# 1-Schematic_video_multiple.net
KiCad netlist of a schematic drawn in EasyEDA
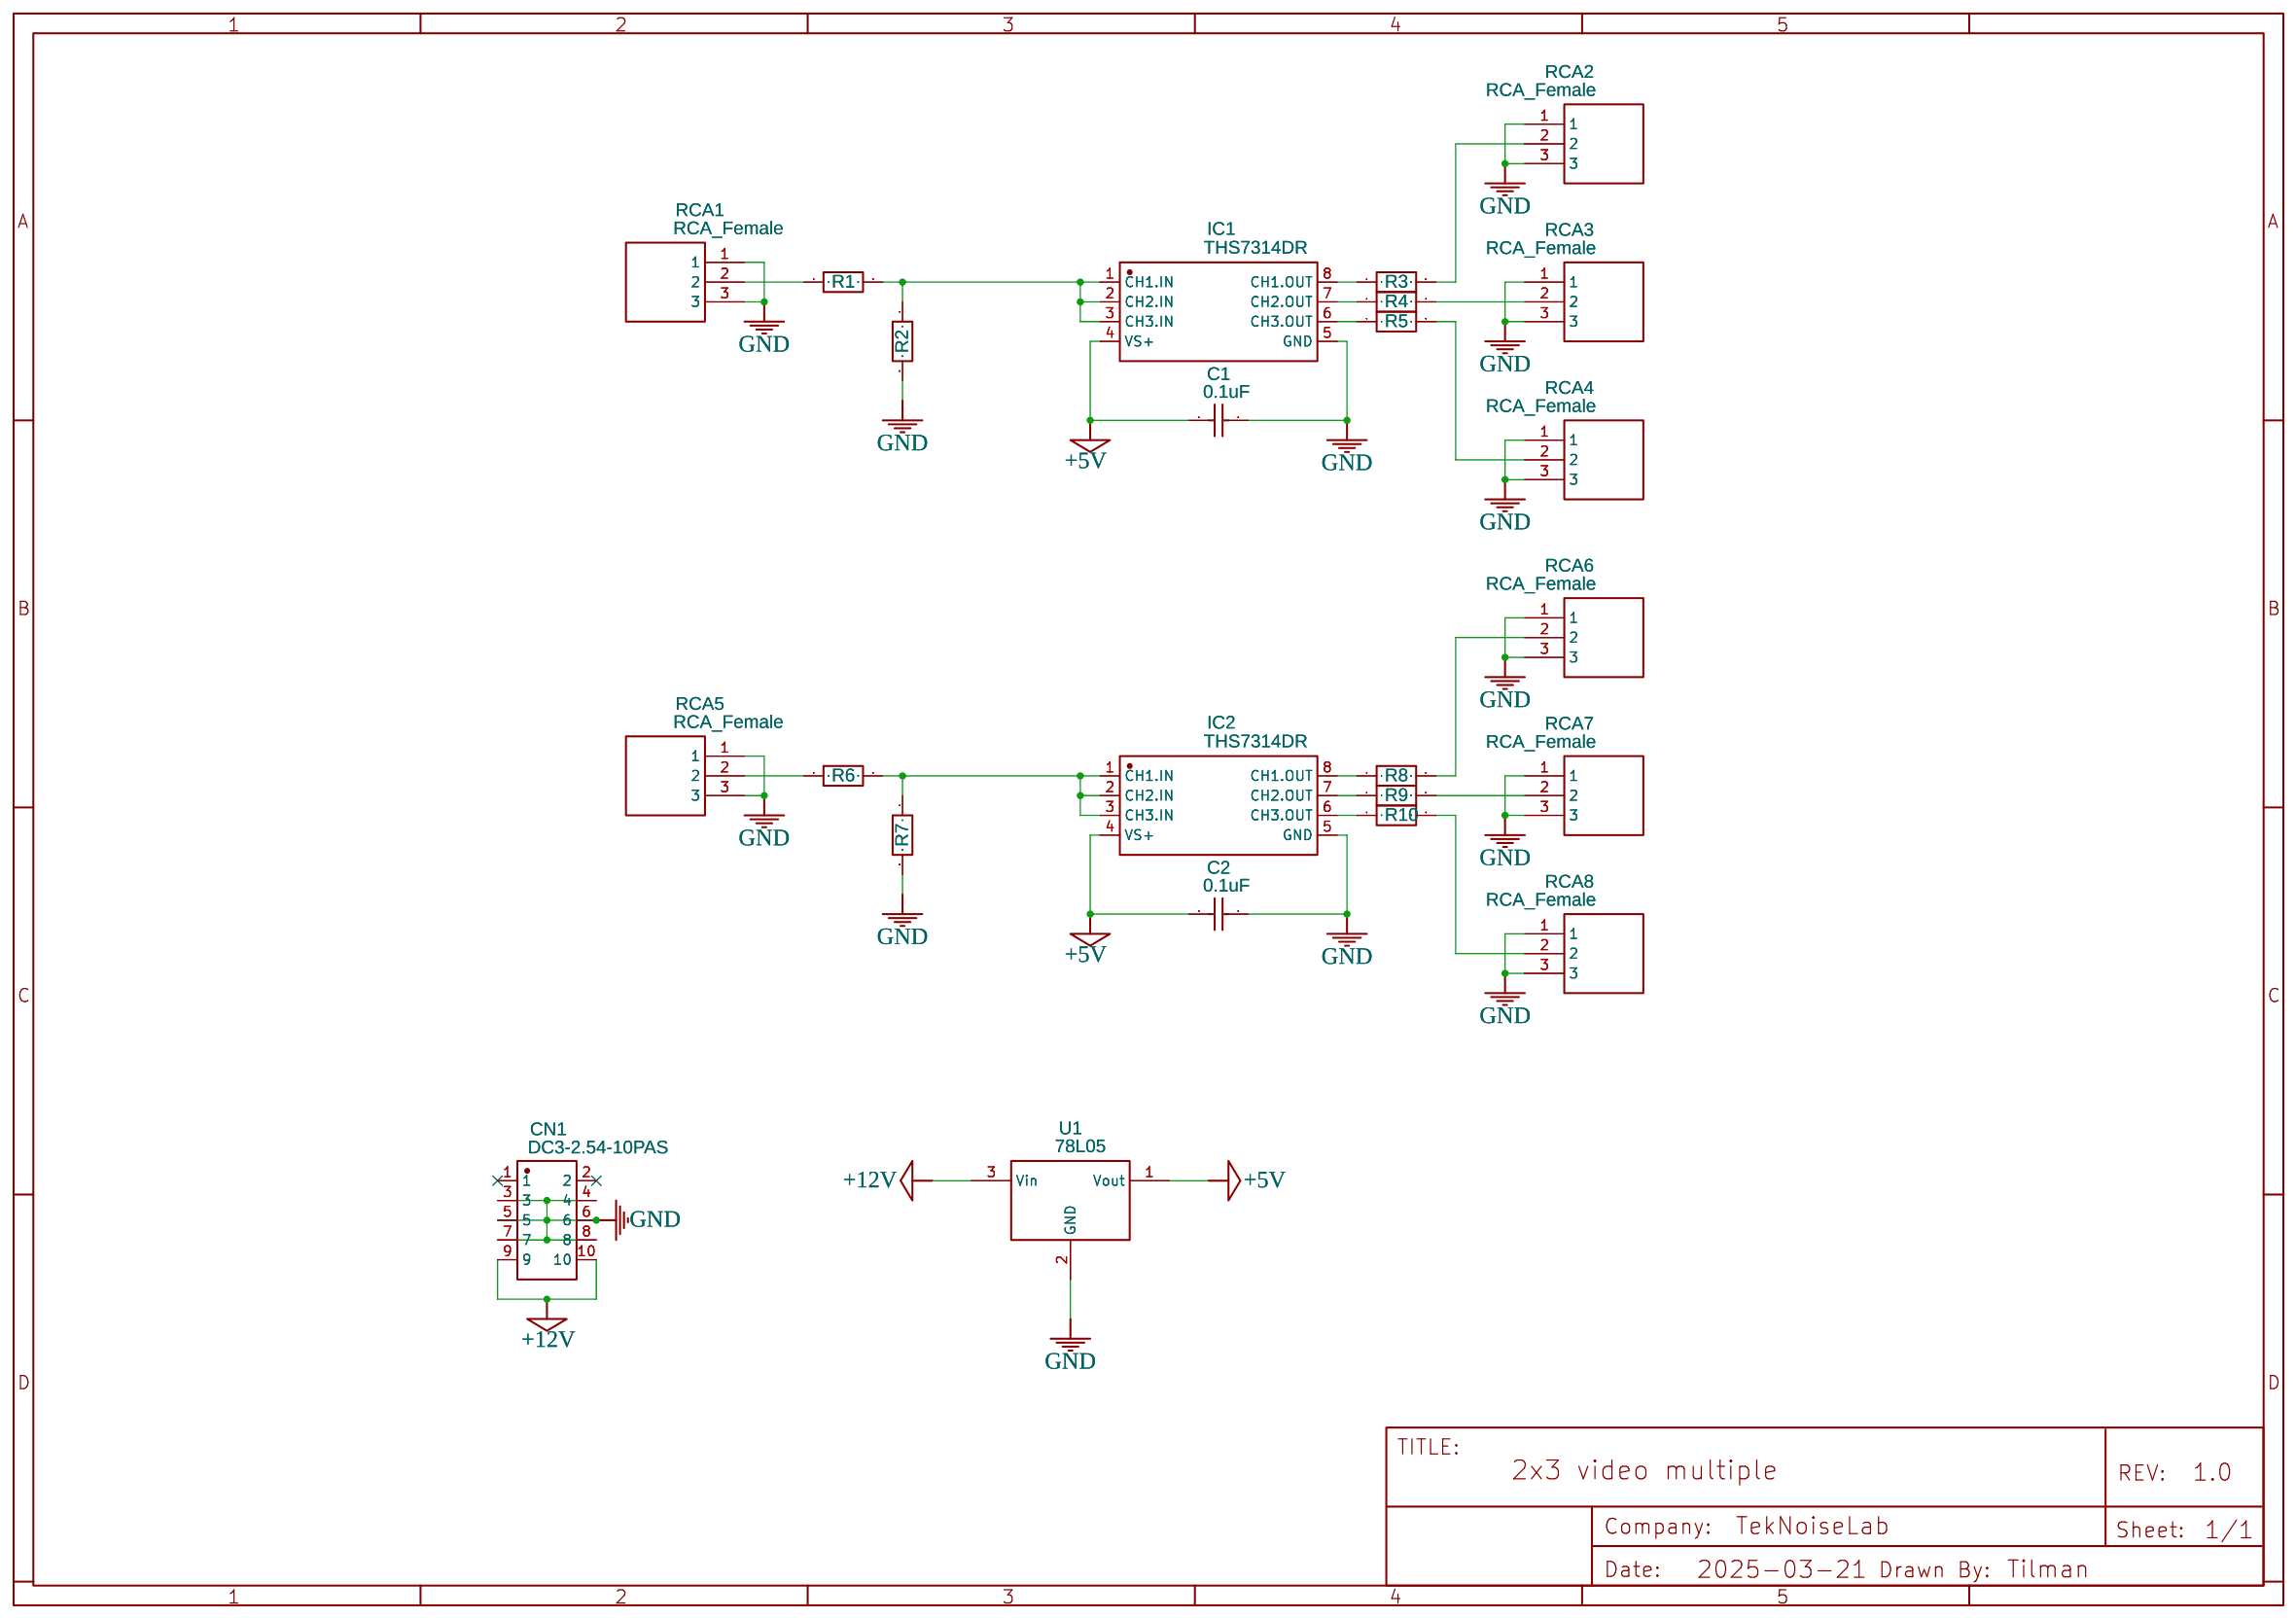
[diagram p0: schematic sheet]

(export (version "E")
  (design (tool "Eeschema 10.0.6"))
  (components
    (comp (ref "C1")
      (value "0.1uF")
      (fields
        (field (name "Manufacturer Part") "0.22uF 5% 100VCalibration capacitor")
        (field (name "Manufacturer") "ReliaPro")
      )
      (libsource (lib "") (part "0.22uF 5% 100VCalibration capacitor"))
    )
    (comp (ref "C2")
      (value "0.1uF")
      (fields
        (field (name "Manufacturer Part") "0.22uF 5% 100VCalibration capacitor")
        (field (name "Manufacturer") "ReliaPro")
      )
      (libsource (lib "") (part "0.22uF 5% 100VCalibration capacitor"))
    )
    (comp (ref "CN1")
      (value "DC3-2.54-10PAS")
      (fields (field (name "Manufacturer") "ZHOURI(洲日)"))
      (libsource (lib "") (part "DC3-2.54-10PAS"))
    )
    (comp (ref "IC1")
      (value "THS7314DR")
      (fields (field (name "Manufacturer") "TI(德州仪器)"))
      (libsource (lib "") (part "THS7314DR"))
    )
    (comp (ref "IC2")
      (value "THS7314DR")
      (fields (field (name "Manufacturer") "TI(德州仪器)"))
      (libsource (lib "") (part "THS7314DR"))
    )
    (comp (ref "R1") (value "75") (libsource (lib "") (part "Res_AXIAL-0.4(1/4W)_US")))
    (comp (ref "R2") (value "75") (libsource (lib "") (part "Res_AXIAL-0.4(1/4W)_US_1")))
    (comp (ref "R3") (value "75") (libsource (lib "") (part "Res_AXIAL-0.4(1/4W)_US")))
    (comp (ref "R4") (value "75") (libsource (lib "") (part "Res_AXIAL-0.4(1/4W)_US")))
    (comp (ref "R5") (value "75") (libsource (lib "") (part "Res_AXIAL-0.4(1/4W)_US")))
    (comp (ref "R6") (value "75") (libsource (lib "") (part "Res_AXIAL-0.4(1/4W)_US")))
    (comp (ref "R7") (value "75") (libsource (lib "") (part "Res_AXIAL-0.4(1/4W)_US_1")))
    (comp (ref "R8") (value "75") (libsource (lib "") (part "Res_AXIAL-0.4(1/4W)_US")))
    (comp (ref "R9") (value "75") (libsource (lib "") (part "Res_AXIAL-0.4(1/4W)_US")))
    (comp (ref "R10") (value "75") (libsource (lib "") (part "Res_AXIAL-0.4(1/4W)_US")))
    (comp (ref "RCA1") (value "RCA_Female") (libsource (lib "") (part "RCA_Female")))
    (comp (ref "RCA2") (value "RCA_Female") (libsource (lib "") (part "RCA_Female_1")))
    (comp (ref "RCA3") (value "RCA_Female") (libsource (lib "") (part "RCA_Female_1")))
    (comp (ref "RCA4") (value "RCA_Female") (libsource (lib "") (part "RCA_Female_1")))
    (comp (ref "RCA5") (value "RCA_Female") (libsource (lib "") (part "RCA_Female")))
    (comp (ref "RCA6") (value "RCA_Female") (libsource (lib "") (part "RCA_Female_1")))
    (comp (ref "RCA7") (value "RCA_Female") (libsource (lib "") (part "RCA_Female_1")))
    (comp (ref "RCA8") (value "RCA_Female") (libsource (lib "") (part "RCA_Female_1")))
    (comp (ref "U1")
      (value "78L05")
      (fields
        (field (name "Manufacturer Part") "SN78L05AT")
        (field (name "Manufacturer") "KODENSHI AUK(光电子)")
      )
      (libsource (lib "") (part "SN78L05AT"))
    )
  )
  (nets
    (net (code "1") (name "+5V") (class "Default")
      (node (ref "C1") (pin "1") (pinfunction "1_1") (pintype "input"))
      (node (ref "C2") (pin "1") (pinfunction "1_1") (pintype "input"))
      (node (ref "IC1") (pin "4") (pinfunction "VS+_4") (pintype "unspecified"))
      (node (ref "IC2") (pin "4") (pinfunction "VS+_4") (pintype "unspecified"))
      (node (ref "U1") (pin "1") (pinfunction "Vout_1") (pintype "unspecified"))
    )
    (net (code "2") (name "+12V") (class "Default")
      (node (ref "CN1") (pin "10") (pinfunction "10_10") (pintype "unspecified"))
      (node (ref "CN1") (pin "9") (pinfunction "9_9") (pintype "unspecified"))
      (node (ref "U1") (pin "3") (pinfunction "Vin_3") (pintype "unspecified"))
    )
    (net (code "3") (name "GND") (class "Default")
      (node (ref "C1") (pin "2") (pinfunction "2_2") (pintype "input"))
      (node (ref "C2") (pin "2") (pinfunction "2_2") (pintype "input"))
      (node (ref "CN1") (pin "3") (pinfunction "3_3") (pintype "unspecified"))
      (node (ref "CN1") (pin "4") (pinfunction "4_4") (pintype "unspecified"))
      (node (ref "CN1") (pin "5") (pinfunction "5_5") (pintype "unspecified"))
      (node (ref "CN1") (pin "6") (pinfunction "6_6") (pintype "unspecified"))
      (node (ref "CN1") (pin "7") (pinfunction "7_7") (pintype "unspecified"))
      (node (ref "CN1") (pin "8") (pinfunction "8_8") (pintype "unspecified"))
      (node (ref "IC1") (pin "5") (pinfunction "GND_5") (pintype "unspecified"))
      (node (ref "IC2") (pin "5") (pinfunction "GND_5") (pintype "unspecified"))
      (node (ref "R2") (pin "2") (pinfunction "2_2") (pintype "unspecified"))
      (node (ref "R7") (pin "2") (pinfunction "2_2") (pintype "unspecified"))
      (node (ref "RCA1") (pin "1") (pinfunction "1_1") (pintype "unspecified"))
      (node (ref "RCA1") (pin "3") (pinfunction "3_3") (pintype "unspecified"))
      (node (ref "RCA2") (pin "1") (pinfunction "1_1") (pintype "unspecified"))
      (node (ref "RCA2") (pin "3") (pinfunction "3_3") (pintype "unspecified"))
      (node (ref "RCA3") (pin "1") (pinfunction "1_1") (pintype "unspecified"))
      (node (ref "RCA3") (pin "3") (pinfunction "3_3") (pintype "unspecified"))
      (node (ref "RCA4") (pin "1") (pinfunction "1_1") (pintype "unspecified"))
      (node (ref "RCA4") (pin "3") (pinfunction "3_3") (pintype "unspecified"))
      (node (ref "RCA5") (pin "1") (pinfunction "1_1") (pintype "unspecified"))
      (node (ref "RCA5") (pin "3") (pinfunction "3_3") (pintype "unspecified"))
      (node (ref "RCA6") (pin "1") (pinfunction "1_1") (pintype "unspecified"))
      (node (ref "RCA6") (pin "3") (pinfunction "3_3") (pintype "unspecified"))
      (node (ref "RCA7") (pin "1") (pinfunction "1_1") (pintype "unspecified"))
      (node (ref "RCA7") (pin "3") (pinfunction "3_3") (pintype "unspecified"))
      (node (ref "RCA8") (pin "1") (pinfunction "1_1") (pintype "unspecified"))
      (node (ref "RCA8") (pin "3") (pinfunction "3_3") (pintype "unspecified"))
      (node (ref "U1") (pin "2") (pinfunction "GND_2") (pintype "unspecified"))
    )
    (net (code "4") (name "Net-(IC1-CH1.IN)") (class "Default")
      (node (ref "IC1") (pin "1") (pinfunction "CH1.IN_1") (pintype "unspecified"))
      (node (ref "IC1") (pin "2") (pinfunction "CH2.IN_2") (pintype "unspecified"))
      (node (ref "IC1") (pin "3") (pinfunction "CH3.IN_3") (pintype "unspecified"))
      (node (ref "R1") (pin "2") (pinfunction "2_2") (pintype "unspecified"))
      (node (ref "R2") (pin "1") (pinfunction "1_1") (pintype "unspecified"))
    )
    (net (code "5") (name "Net-(IC1-CH1.OUT)") (class "Default")
      (node (ref "IC1") (pin "8") (pinfunction "CH1.OUT_8") (pintype "unspecified"))
      (node (ref "R3") (pin "1") (pinfunction "1_1") (pintype "unspecified"))
    )
    (net (code "6") (name "Net-(IC1-CH2.OUT)") (class "Default")
      (node (ref "IC1") (pin "7") (pinfunction "CH2.OUT_7") (pintype "unspecified"))
      (node (ref "R4") (pin "1") (pinfunction "1_1") (pintype "unspecified"))
    )
    (net (code "7") (name "Net-(IC1-CH3.OUT)") (class "Default")
      (node (ref "IC1") (pin "6") (pinfunction "CH3.OUT_6") (pintype "unspecified"))
      (node (ref "R5") (pin "1") (pinfunction "1_1") (pintype "unspecified"))
    )
    (net (code "8") (name "Net-(IC2-CH1.IN)") (class "Default")
      (node (ref "IC2") (pin "1") (pinfunction "CH1.IN_1") (pintype "unspecified"))
      (node (ref "IC2") (pin "2") (pinfunction "CH2.IN_2") (pintype "unspecified"))
      (node (ref "IC2") (pin "3") (pinfunction "CH3.IN_3") (pintype "unspecified"))
      (node (ref "R6") (pin "2") (pinfunction "2_2") (pintype "unspecified"))
      (node (ref "R7") (pin "1") (pinfunction "1_1") (pintype "unspecified"))
    )
    (net (code "9") (name "Net-(IC2-CH1.OUT)") (class "Default")
      (node (ref "IC2") (pin "8") (pinfunction "CH1.OUT_8") (pintype "unspecified"))
      (node (ref "R8") (pin "1") (pinfunction "1_1") (pintype "unspecified"))
    )
    (net (code "10") (name "Net-(IC2-CH2.OUT)") (class "Default")
      (node (ref "IC2") (pin "7") (pinfunction "CH2.OUT_7") (pintype "unspecified"))
      (node (ref "R9") (pin "1") (pinfunction "1_1") (pintype "unspecified"))
    )
    (net (code "11") (name "Net-(IC2-CH3.OUT)") (class "Default")
      (node (ref "IC2") (pin "6") (pinfunction "CH3.OUT_6") (pintype "unspecified"))
      (node (ref "R10") (pin "1") (pinfunction "1_1") (pintype "unspecified"))
    )
    (net (code "12") (name "Net-(R1-Pad1)") (class "Default")
      (node (ref "R1") (pin "1") (pinfunction "1_1") (pintype "unspecified"))
      (node (ref "RCA1") (pin "2") (pinfunction "2_2") (pintype "unspecified"))
    )
    (net (code "13") (name "Net-(R3-Pad2)") (class "Default")
      (node (ref "R3") (pin "2") (pinfunction "2_2") (pintype "unspecified"))
      (node (ref "RCA2") (pin "2") (pinfunction "2_2") (pintype "unspecified"))
    )
    (net (code "14") (name "Net-(R4-Pad2)") (class "Default")
      (node (ref "R4") (pin "2") (pinfunction "2_2") (pintype "unspecified"))
      (node (ref "RCA3") (pin "2") (pinfunction "2_2") (pintype "unspecified"))
    )
    (net (code "15") (name "Net-(R5-Pad2)") (class "Default")
      (node (ref "R5") (pin "2") (pinfunction "2_2") (pintype "unspecified"))
      (node (ref "RCA4") (pin "2") (pinfunction "2_2") (pintype "unspecified"))
    )
    (net (code "16") (name "Net-(R6-Pad1)") (class "Default")
      (node (ref "R6") (pin "1") (pinfunction "1_1") (pintype "unspecified"))
      (node (ref "RCA5") (pin "2") (pinfunction "2_2") (pintype "unspecified"))
    )
    (net (code "17") (name "Net-(R8-Pad2)") (class "Default")
      (node (ref "R8") (pin "2") (pinfunction "2_2") (pintype "unspecified"))
      (node (ref "RCA6") (pin "2") (pinfunction "2_2") (pintype "unspecified"))
    )
    (net (code "18") (name "Net-(R9-Pad2)") (class "Default")
      (node (ref "R9") (pin "2") (pinfunction "2_2") (pintype "unspecified"))
      (node (ref "RCA7") (pin "2") (pinfunction "2_2") (pintype "unspecified"))
    )
    (net (code "19") (name "Net-(R10-Pad2)") (class "Default")
      (node (ref "R10") (pin "2") (pinfunction "2_2") (pintype "unspecified"))
      (node (ref "RCA8") (pin "2") (pinfunction "2_2") (pintype "unspecified"))
    )
    (net (code "20") (name "unconnected-(CN1-Pad1)") (class "Default")
      (node (ref "CN1") (pin "1") (pinfunction "1_1") (pintype "unspecified+no_connect"))
    )
    (net (code "21") (name "unconnected-(CN1-Pad2)") (class "Default")
      (node (ref "CN1") (pin "2") (pinfunction "2_2") (pintype "unspecified+no_connect"))
    )
  )
)
